# COMECA_TestSCH.net
KiCad netlist of a schematic drawn in Altium Designer
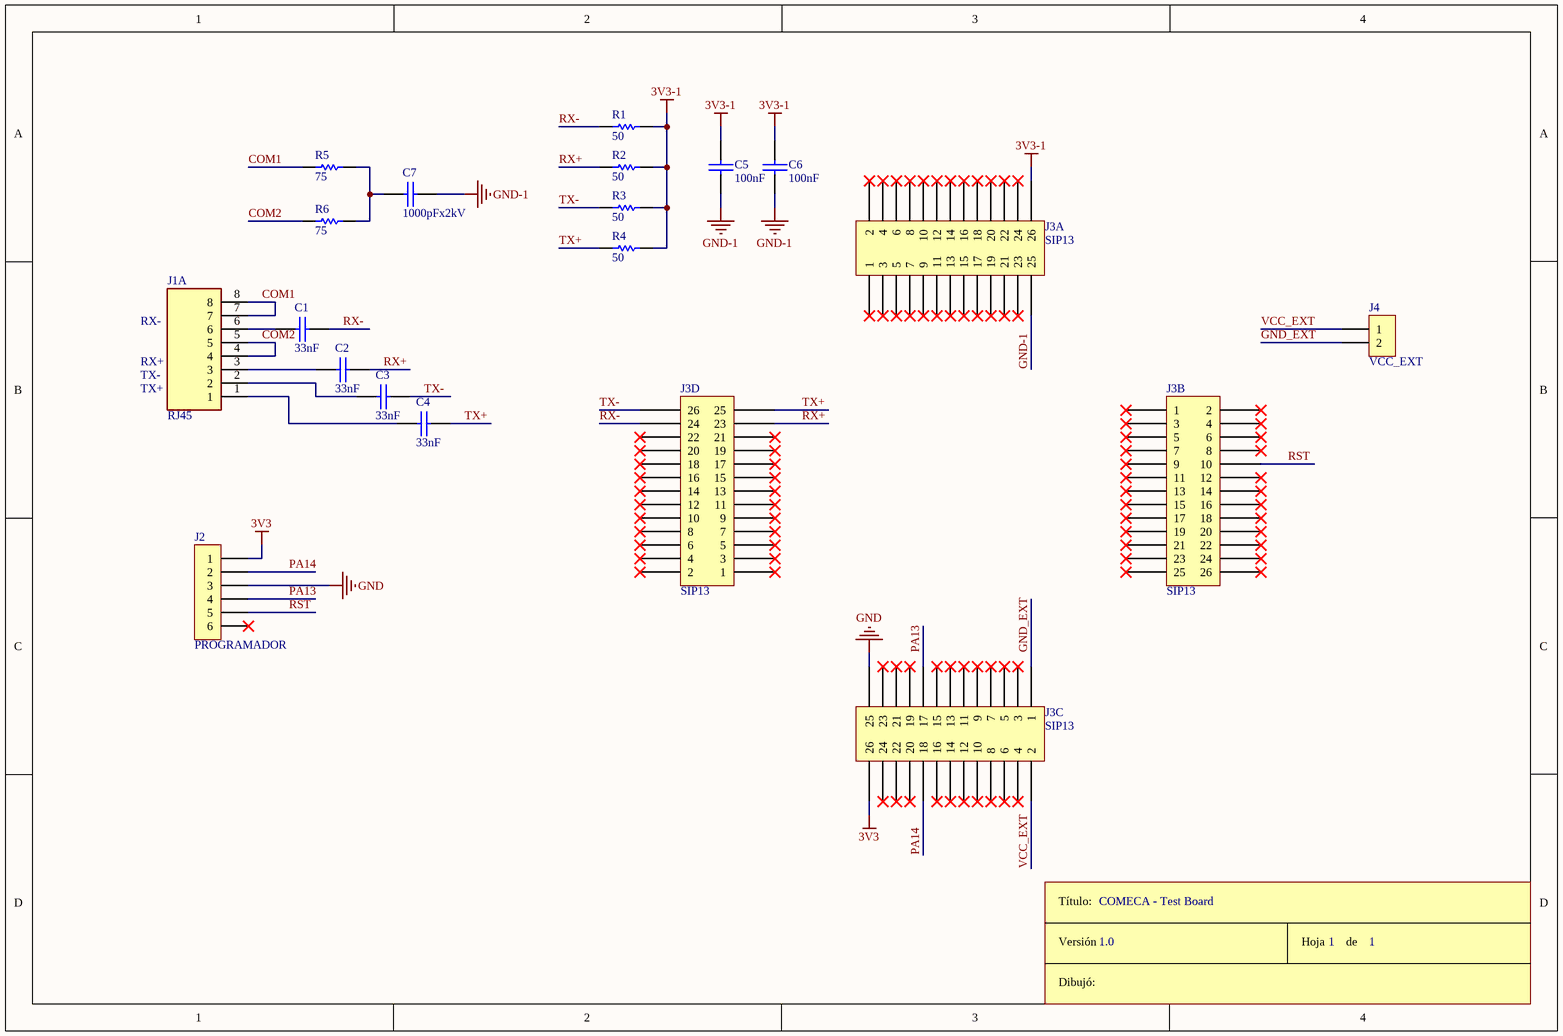
[diagram p0: COMECA_TestSCH.SchDoc]

(export (version "E")
  (design (tool "Eeschema 10.0.6"))
  (components
    (comp (ref "C1") (value "33nF") (footprint "CAP100") (libsource (lib "LIBEBAL") (part "CAP")))
    (comp (ref "C2") (value "33nF") (footprint "CAP100") (libsource (lib "LIBEBAL") (part "CAP")))
    (comp (ref "C3") (value "33nF") (footprint "CAP100") (libsource (lib "LIBEBAL") (part "CAP")))
    (comp (ref "C4") (value "33nF") (footprint "CAP100") (libsource (lib "LIBEBAL") (part "CAP")))
    (comp (ref "C5") (value "100nF") (footprint "CAP100") (libsource (lib "LIBEBAL") (part "CAP")))
    (comp (ref "C6") (value "100nF") (footprint "CAP100") (libsource (lib "LIBEBAL") (part "CAP")))
    (comp (ref "C7") (value "1000pFx2kV") (footprint "CAP100") (libsource (lib "LIBEBAL") (part "CAP")))
    (comp (ref "J1A")
      (value "RJ45")
      (footprint "CUI_CRJ032-1-TH")
      (description "8P8C, Single Port, Horizontal, Unshielded, No LED, Through Hole, RJ45 Modular Connector")
      (fields (field (name "MP") "CRJ032-1-TH") (field (name "MF") "CUI Devices"))
      (libsource (lib "CRJ032-1-TH") (part "CRJ032-1-TH"))
    )
    (comp (ref "J2") (value "PROGRAMADOR") (footprint "SIP6") (libsource (lib "LIBEBAL") (part "CON6")))
    (comp (ref "J3A")
      (value "SIP13")
      (footprint "SIP13*2 - HDR")
      (libsource (lib "AditionalComponents") (part "CON13*2"))
    )
    (comp (ref "J3B") (value "SIP13") (footprint "SIP13*2 - HDR") (libsource (lib "") (part "CON13*2_1")))
    (comp (ref "J3C") (value "SIP13") (footprint "SIP13*2 - HDR") (libsource (lib "") (part "CON13*2_3")))
    (comp (ref "J3D") (value "SIP13") (footprint "SIP13*2 - HDR") (libsource (lib "") (part "CON13*2_2")))
    (comp (ref "J4") (value "VCC_EXT") (footprint "SIP2") (libsource (lib "LIBEBAL") (part "CON2")))
    (comp (ref "R1") (value "50") (footprint "RES400") (libsource (lib "LIBEBAL") (part "RES")))
    (comp (ref "R2") (value "50") (footprint "RES400") (libsource (lib "LIBEBAL") (part "RES")))
    (comp (ref "R3") (value "50") (footprint "RES400") (libsource (lib "LIBEBAL") (part "RES")))
    (comp (ref "R4") (value "50") (footprint "RES400") (libsource (lib "LIBEBAL") (part "RES")))
    (comp (ref "R5") (value "75") (footprint "RES400") (libsource (lib "LIBEBAL") (part "RES")))
    (comp (ref "R6") (value "75") (footprint "RES400") (libsource (lib "LIBEBAL") (part "RES")))
    (comp (ref "ROT1") (value "Rótulo") (libsource (lib "LIB PIO IX") (part "Rótulo")))
  )
  (nets
    (net (code "1") (name "/COM1") (class "Default")
      (node (ref "J1A") (pin "7") (pinfunction "7_7") (pintype "passive"))
      (node (ref "J1A") (pin "8") (pinfunction "8_8") (pintype "passive"))
      (node (ref "R5") (pin "2") (pinfunction "2_2") (pintype "passive"))
    )
    (net (code "2") (name "/COM2") (class "Default")
      (node (ref "J1A") (pin "4") (pinfunction "4_4") (pintype "passive"))
      (node (ref "J1A") (pin "5") (pinfunction "5_5") (pintype "passive"))
      (node (ref "R6") (pin "1") (pinfunction "1_1") (pintype "passive"))
    )
    (net (code "3") (name "/GND_EXT") (class "Default")
      (node (ref "J3C") (pin "1") (pinfunction "1_1") (pintype "passive"))
      (node (ref "J4") (pin "2") (pinfunction "2_2") (pintype "passive"))
    )
    (net (code "4") (name "/PA13") (class "Default")
      (node (ref "J2") (pin "4") (pinfunction "4_4") (pintype "passive"))
      (node (ref "J3C") (pin "17") (pinfunction "17_17") (pintype "passive"))
    )
    (net (code "5") (name "/PA14") (class "Default")
      (node (ref "J2") (pin "2") (pinfunction "2_2") (pintype "passive"))
      (node (ref "J3C") (pin "18") (pinfunction "18_18") (pintype "passive"))
    )
    (net (code "6") (name "/RST") (class "Default")
      (node (ref "J2") (pin "5") (pinfunction "5_5") (pintype "passive"))
      (node (ref "J3B") (pin "10") (pinfunction "10_10") (pintype "passive"))
    )
    (net (code "7") (name "/RX+") (class "Default")
      (node (ref "C2") (pin "2") (pinfunction "2_2") (pintype "passive"))
      (node (ref "J3D") (pin "23") (pinfunction "23_23") (pintype "passive"))
      (node (ref "R2") (pin "1") (pinfunction "1_1") (pintype "passive"))
    )
    (net (code "8") (name "/RX-") (class "Default")
      (node (ref "C1") (pin "2") (pinfunction "2_2") (pintype "passive"))
      (node (ref "J3D") (pin "24") (pinfunction "24_24") (pintype "passive"))
      (node (ref "R1") (pin "1") (pinfunction "1_1") (pintype "passive"))
    )
    (net (code "9") (name "/TX+") (class "Default")
      (node (ref "C4") (pin "2") (pinfunction "2_2") (pintype "passive"))
      (node (ref "J3D") (pin "25") (pinfunction "25_25") (pintype "passive"))
      (node (ref "R4") (pin "1") (pinfunction "1_1") (pintype "passive"))
    )
    (net (code "10") (name "/TX-") (class "Default")
      (node (ref "C3") (pin "2") (pinfunction "2_2") (pintype "passive"))
      (node (ref "J3D") (pin "26") (pinfunction "26_26") (pintype "passive"))
      (node (ref "R3") (pin "1") (pinfunction "1_1") (pintype "passive"))
    )
    (net (code "11") (name "/VCC_EXT") (class "Default")
      (node (ref "J3C") (pin "2") (pinfunction "2_2") (pintype "passive"))
      (node (ref "J4") (pin "1") (pinfunction "1_1") (pintype "passive"))
    )
    (net (code "12") (name "3V3") (class "Default")
      (node (ref "J2") (pin "1") (pinfunction "1_1") (pintype "passive"))
      (node (ref "J3C") (pin "26") (pinfunction "26_26") (pintype "passive"))
    )
    (net (code "13") (name "3V3-1") (class "Default")
      (node (ref "C5") (pin "1") (pinfunction "1_1") (pintype "passive"))
      (node (ref "C6") (pin "1") (pinfunction "1_1") (pintype "passive"))
      (node (ref "J3A") (pin "26") (pinfunction "26_26") (pintype "passive"))
      (node (ref "R1") (pin "2") (pinfunction "2_2") (pintype "passive"))
      (node (ref "R2") (pin "2") (pinfunction "2_2") (pintype "passive"))
      (node (ref "R3") (pin "2") (pinfunction "2_2") (pintype "passive"))
      (node (ref "R4") (pin "2") (pinfunction "2_2") (pintype "passive"))
    )
    (net (code "14") (name "GND") (class "Default")
      (node (ref "J2") (pin "3") (pinfunction "3_3") (pintype "passive"))
      (node (ref "J3C") (pin "25") (pinfunction "25_25") (pintype "passive"))
    )
    (net (code "15") (name "GND-1") (class "Default")
      (node (ref "C5") (pin "2") (pinfunction "2_2") (pintype "passive"))
      (node (ref "C6") (pin "2") (pinfunction "2_2") (pintype "passive"))
      (node (ref "C7") (pin "2") (pinfunction "2_2") (pintype "passive"))
      (node (ref "J3A") (pin "25") (pinfunction "25_25") (pintype "passive"))
    )
    (net (code "16") (name "Net-(C1-Pad1)") (class "Default")
      (node (ref "C1") (pin "1") (pinfunction "1_1") (pintype "passive"))
      (node (ref "J1A") (pin "6") (pinfunction "6_6") (pintype "passive"))
    )
    (net (code "17") (name "Net-(C2-Pad1)") (class "Default")
      (node (ref "C2") (pin "1") (pinfunction "1_1") (pintype "passive"))
      (node (ref "J1A") (pin "3") (pinfunction "3_3") (pintype "passive"))
    )
    (net (code "18") (name "Net-(C3-Pad1)") (class "Default")
      (node (ref "C3") (pin "1") (pinfunction "1_1") (pintype "passive"))
      (node (ref "J1A") (pin "2") (pinfunction "2_2") (pintype "passive"))
    )
    (net (code "19") (name "Net-(C4-Pad1)") (class "Default")
      (node (ref "C4") (pin "1") (pinfunction "1_1") (pintype "passive"))
      (node (ref "J1A") (pin "1") (pinfunction "1_1") (pintype "passive"))
    )
    (net (code "20") (name "Net-(C7-Pad1)") (class "Default")
      (node (ref "C7") (pin "1") (pinfunction "1_1") (pintype "passive"))
      (node (ref "R5") (pin "1") (pinfunction "1_1") (pintype "passive"))
      (node (ref "R6") (pin "2") (pinfunction "2_2") (pintype "passive"))
    )
    (net (code "21") (name "unconnected-(J2-Pad6)") (class "Default")
      (node (ref "J2") (pin "6") (pinfunction "6_6") (pintype "passive+no_connect"))
    )
    (net (code "22") (name "unconnected-(J3A-Pad1)") (class "Default")
      (node (ref "J3A") (pin "1") (pinfunction "1_1") (pintype "passive+no_connect"))
    )
    (net (code "23") (name "unconnected-(J3A-Pad2)") (class "Default")
      (node (ref "J3A") (pin "2") (pinfunction "2_2") (pintype "passive+no_connect"))
    )
    (net (code "24") (name "unconnected-(J3A-Pad3)") (class "Default")
      (node (ref "J3A") (pin "3") (pinfunction "3_3") (pintype "passive+no_connect"))
    )
    (net (code "25") (name "unconnected-(J3A-Pad4)") (class "Default")
      (node (ref "J3A") (pin "4") (pinfunction "4_4") (pintype "passive+no_connect"))
    )
    (net (code "26") (name "unconnected-(J3A-Pad5)") (class "Default")
      (node (ref "J3A") (pin "5") (pinfunction "5_5") (pintype "passive+no_connect"))
    )
    (net (code "27") (name "unconnected-(J3A-Pad6)") (class "Default")
      (node (ref "J3A") (pin "6") (pinfunction "6_6") (pintype "passive+no_connect"))
    )
    (net (code "28") (name "unconnected-(J3A-Pad7)") (class "Default")
      (node (ref "J3A") (pin "7") (pinfunction "7_7") (pintype "passive+no_connect"))
    )
    (net (code "29") (name "unconnected-(J3A-Pad8)") (class "Default")
      (node (ref "J3A") (pin "8") (pinfunction "8_8") (pintype "passive+no_connect"))
    )
    (net (code "30") (name "unconnected-(J3A-Pad9)") (class "Default")
      (node (ref "J3A") (pin "9") (pinfunction "9_9") (pintype "passive+no_connect"))
    )
    (net (code "31") (name "unconnected-(J3A-Pad10)") (class "Default")
      (node (ref "J3A") (pin "10") (pinfunction "10_10") (pintype "passive+no_connect"))
    )
    (net (code "32") (name "unconnected-(J3A-Pad11)") (class "Default")
      (node (ref "J3A") (pin "11") (pinfunction "11_11") (pintype "passive+no_connect"))
    )
    (net (code "33") (name "unconnected-(J3A-Pad12)") (class "Default")
      (node (ref "J3A") (pin "12") (pinfunction "12_12") (pintype "passive+no_connect"))
    )
    (net (code "34") (name "unconnected-(J3A-Pad13)") (class "Default")
      (node (ref "J3A") (pin "13") (pinfunction "13_13") (pintype "passive+no_connect"))
    )
    (net (code "35") (name "unconnected-(J3A-Pad14)") (class "Default")
      (node (ref "J3A") (pin "14") (pinfunction "14_14") (pintype "passive+no_connect"))
    )
    (net (code "36") (name "unconnected-(J3A-Pad15)") (class "Default")
      (node (ref "J3A") (pin "15") (pinfunction "15_15") (pintype "passive+no_connect"))
    )
    (net (code "37") (name "unconnected-(J3A-Pad16)") (class "Default")
      (node (ref "J3A") (pin "16") (pinfunction "16_16") (pintype "passive+no_connect"))
    )
    (net (code "38") (name "unconnected-(J3A-Pad17)") (class "Default")
      (node (ref "J3A") (pin "17") (pinfunction "17_17") (pintype "passive+no_connect"))
    )
    (net (code "39") (name "unconnected-(J3A-Pad18)") (class "Default")
      (node (ref "J3A") (pin "18") (pinfunction "18_18") (pintype "passive+no_connect"))
    )
    (net (code "40") (name "unconnected-(J3A-Pad19)") (class "Default")
      (node (ref "J3A") (pin "19") (pinfunction "19_19") (pintype "passive+no_connect"))
    )
    (net (code "41") (name "unconnected-(J3A-Pad20)") (class "Default")
      (node (ref "J3A") (pin "20") (pinfunction "20_20") (pintype "passive+no_connect"))
    )
    (net (code "42") (name "unconnected-(J3A-Pad21)") (class "Default")
      (node (ref "J3A") (pin "21") (pinfunction "21_21") (pintype "passive+no_connect"))
    )
    (net (code "43") (name "unconnected-(J3A-Pad22)") (class "Default")
      (node (ref "J3A") (pin "22") (pinfunction "22_22") (pintype "passive+no_connect"))
    )
    (net (code "44") (name "unconnected-(J3A-Pad23)") (class "Default")
      (node (ref "J3A") (pin "23") (pinfunction "23_23") (pintype "passive+no_connect"))
    )
    (net (code "45") (name "unconnected-(J3A-Pad24)") (class "Default")
      (node (ref "J3A") (pin "24") (pinfunction "24_24") (pintype "passive+no_connect"))
    )
    (net (code "46") (name "unconnected-(J3B-Pad1)") (class "Default")
      (node (ref "J3B") (pin "1") (pinfunction "1_1") (pintype "passive+no_connect"))
    )
    (net (code "47") (name "unconnected-(J3B-Pad2)") (class "Default")
      (node (ref "J3B") (pin "2") (pinfunction "2_2") (pintype "passive+no_connect"))
    )
    (net (code "48") (name "unconnected-(J3B-Pad3)") (class "Default")
      (node (ref "J3B") (pin "3") (pinfunction "3_3") (pintype "passive+no_connect"))
    )
    (net (code "49") (name "unconnected-(J3B-Pad4)") (class "Default")
      (node (ref "J3B") (pin "4") (pinfunction "4_4") (pintype "passive+no_connect"))
    )
    (net (code "50") (name "unconnected-(J3B-Pad5)") (class "Default")
      (node (ref "J3B") (pin "5") (pinfunction "5_5") (pintype "passive+no_connect"))
    )
    (net (code "51") (name "unconnected-(J3B-Pad6)") (class "Default")
      (node (ref "J3B") (pin "6") (pinfunction "6_6") (pintype "passive+no_connect"))
    )
    (net (code "52") (name "unconnected-(J3B-Pad7)") (class "Default")
      (node (ref "J3B") (pin "7") (pinfunction "7_7") (pintype "passive+no_connect"))
    )
    (net (code "53") (name "unconnected-(J3B-Pad8)") (class "Default")
      (node (ref "J3B") (pin "8") (pinfunction "8_8") (pintype "passive+no_connect"))
    )
    (net (code "54") (name "unconnected-(J3B-Pad9)") (class "Default")
      (node (ref "J3B") (pin "9") (pinfunction "9_9") (pintype "passive+no_connect"))
    )
    (net (code "55") (name "unconnected-(J3B-Pad11)") (class "Default")
      (node (ref "J3B") (pin "11") (pinfunction "11_11") (pintype "passive+no_connect"))
    )
    (net (code "56") (name "unconnected-(J3B-Pad12)") (class "Default")
      (node (ref "J3B") (pin "12") (pinfunction "12_12") (pintype "passive+no_connect"))
    )
    (net (code "57") (name "unconnected-(J3B-Pad13)") (class "Default")
      (node (ref "J3B") (pin "13") (pinfunction "13_13") (pintype "passive+no_connect"))
    )
    (net (code "58") (name "unconnected-(J3B-Pad14)") (class "Default")
      (node (ref "J3B") (pin "14") (pinfunction "14_14") (pintype "passive+no_connect"))
    )
    (net (code "59") (name "unconnected-(J3B-Pad15)") (class "Default")
      (node (ref "J3B") (pin "15") (pinfunction "15_15") (pintype "passive+no_connect"))
    )
    (net (code "60") (name "unconnected-(J3B-Pad16)") (class "Default")
      (node (ref "J3B") (pin "16") (pinfunction "16_16") (pintype "passive+no_connect"))
    )
    (net (code "61") (name "unconnected-(J3B-Pad17)") (class "Default")
      (node (ref "J3B") (pin "17") (pinfunction "17_17") (pintype "passive+no_connect"))
    )
    (net (code "62") (name "unconnected-(J3B-Pad18)") (class "Default")
      (node (ref "J3B") (pin "18") (pinfunction "18_18") (pintype "passive+no_connect"))
    )
    (net (code "63") (name "unconnected-(J3B-Pad19)") (class "Default")
      (node (ref "J3B") (pin "19") (pinfunction "19_19") (pintype "passive+no_connect"))
    )
    (net (code "64") (name "unconnected-(J3B-Pad20)") (class "Default")
      (node (ref "J3B") (pin "20") (pinfunction "20_20") (pintype "passive+no_connect"))
    )
    (net (code "65") (name "unconnected-(J3B-Pad21)") (class "Default")
      (node (ref "J3B") (pin "21") (pinfunction "21_21") (pintype "passive+no_connect"))
    )
    (net (code "66") (name "unconnected-(J3B-Pad22)") (class "Default")
      (node (ref "J3B") (pin "22") (pinfunction "22_22") (pintype "passive+no_connect"))
    )
    (net (code "67") (name "unconnected-(J3B-Pad23)") (class "Default")
      (node (ref "J3B") (pin "23") (pinfunction "23_23") (pintype "passive+no_connect"))
    )
    (net (code "68") (name "unconnected-(J3B-Pad24)") (class "Default")
      (node (ref "J3B") (pin "24") (pinfunction "24_24") (pintype "passive+no_connect"))
    )
    (net (code "69") (name "unconnected-(J3B-Pad25)") (class "Default")
      (node (ref "J3B") (pin "25") (pinfunction "25_25") (pintype "passive+no_connect"))
    )
    (net (code "70") (name "unconnected-(J3B-Pad26)") (class "Default")
      (node (ref "J3B") (pin "26") (pinfunction "26_26") (pintype "passive+no_connect"))
    )
    (net (code "71") (name "unconnected-(J3C-Pad3)") (class "Default")
      (node (ref "J3C") (pin "3") (pinfunction "3_3") (pintype "passive+no_connect"))
    )
    (net (code "72") (name "unconnected-(J3C-Pad4)") (class "Default")
      (node (ref "J3C") (pin "4") (pinfunction "4_4") (pintype "passive+no_connect"))
    )
    (net (code "73") (name "unconnected-(J3C-Pad5)") (class "Default")
      (node (ref "J3C") (pin "5") (pinfunction "5_5") (pintype "passive+no_connect"))
    )
    (net (code "74") (name "unconnected-(J3C-Pad6)") (class "Default")
      (node (ref "J3C") (pin "6") (pinfunction "6_6") (pintype "passive+no_connect"))
    )
    (net (code "75") (name "unconnected-(J3C-Pad7)") (class "Default")
      (node (ref "J3C") (pin "7") (pinfunction "7_7") (pintype "passive+no_connect"))
    )
    (net (code "76") (name "unconnected-(J3C-Pad8)") (class "Default")
      (node (ref "J3C") (pin "8") (pinfunction "8_8") (pintype "passive+no_connect"))
    )
    (net (code "77") (name "unconnected-(J3C-Pad9)") (class "Default")
      (node (ref "J3C") (pin "9") (pinfunction "9_9") (pintype "passive+no_connect"))
    )
    (net (code "78") (name "unconnected-(J3C-Pad10)") (class "Default")
      (node (ref "J3C") (pin "10") (pinfunction "10_10") (pintype "passive+no_connect"))
    )
    (net (code "79") (name "unconnected-(J3C-Pad11)") (class "Default")
      (node (ref "J3C") (pin "11") (pinfunction "11_11") (pintype "passive+no_connect"))
    )
    (net (code "80") (name "unconnected-(J3C-Pad12)") (class "Default")
      (node (ref "J3C") (pin "12") (pinfunction "12_12") (pintype "passive+no_connect"))
    )
    (net (code "81") (name "unconnected-(J3C-Pad13)") (class "Default")
      (node (ref "J3C") (pin "13") (pinfunction "13_13") (pintype "passive+no_connect"))
    )
    (net (code "82") (name "unconnected-(J3C-Pad14)") (class "Default")
      (node (ref "J3C") (pin "14") (pinfunction "14_14") (pintype "passive+no_connect"))
    )
    (net (code "83") (name "unconnected-(J3C-Pad15)") (class "Default")
      (node (ref "J3C") (pin "15") (pinfunction "15_15") (pintype "passive+no_connect"))
    )
    (net (code "84") (name "unconnected-(J3C-Pad16)") (class "Default")
      (node (ref "J3C") (pin "16") (pinfunction "16_16") (pintype "passive+no_connect"))
    )
    (net (code "85") (name "unconnected-(J3C-Pad19)") (class "Default")
      (node (ref "J3C") (pin "19") (pinfunction "19_19") (pintype "passive+no_connect"))
    )
    (net (code "86") (name "unconnected-(J3C-Pad20)") (class "Default")
      (node (ref "J3C") (pin "20") (pinfunction "20_20") (pintype "passive+no_connect"))
    )
    (net (code "87") (name "unconnected-(J3C-Pad21)") (class "Default")
      (node (ref "J3C") (pin "21") (pinfunction "21_21") (pintype "passive+no_connect"))
    )
    (net (code "88") (name "unconnected-(J3C-Pad22)") (class "Default")
      (node (ref "J3C") (pin "22") (pinfunction "22_22") (pintype "passive+no_connect"))
    )
    (net (code "89") (name "unconnected-(J3C-Pad23)") (class "Default")
      (node (ref "J3C") (pin "23") (pinfunction "23_23") (pintype "passive+no_connect"))
    )
    (net (code "90") (name "unconnected-(J3C-Pad24)") (class "Default")
      (node (ref "J3C") (pin "24") (pinfunction "24_24") (pintype "passive+no_connect"))
    )
    (net (code "91") (name "unconnected-(J3D-Pad1)") (class "Default")
      (node (ref "J3D") (pin "1") (pinfunction "1_1") (pintype "passive+no_connect"))
    )
    (net (code "92") (name "unconnected-(J3D-Pad2)") (class "Default")
      (node (ref "J3D") (pin "2") (pinfunction "2_2") (pintype "passive+no_connect"))
    )
    (net (code "93") (name "unconnected-(J3D-Pad3)") (class "Default")
      (node (ref "J3D") (pin "3") (pinfunction "3_3") (pintype "passive+no_connect"))
    )
    (net (code "94") (name "unconnected-(J3D-Pad4)") (class "Default")
      (node (ref "J3D") (pin "4") (pinfunction "4_4") (pintype "passive+no_connect"))
    )
    (net (code "95") (name "unconnected-(J3D-Pad5)") (class "Default")
      (node (ref "J3D") (pin "5") (pinfunction "5_5") (pintype "passive+no_connect"))
    )
    (net (code "96") (name "unconnected-(J3D-Pad6)") (class "Default")
      (node (ref "J3D") (pin "6") (pinfunction "6_6") (pintype "passive+no_connect"))
    )
    (net (code "97") (name "unconnected-(J3D-Pad7)") (class "Default")
      (node (ref "J3D") (pin "7") (pinfunction "7_7") (pintype "passive+no_connect"))
    )
    (net (code "98") (name "unconnected-(J3D-Pad8)") (class "Default")
      (node (ref "J3D") (pin "8") (pinfunction "8_8") (pintype "passive+no_connect"))
    )
    (net (code "99") (name "unconnected-(J3D-Pad9)") (class "Default")
      (node (ref "J3D") (pin "9") (pinfunction "9_9") (pintype "passive+no_connect"))
    )
    (net (code "100") (name "unconnected-(J3D-Pad10)") (class "Default")
      (node (ref "J3D") (pin "10") (pinfunction "10_10") (pintype "passive+no_connect"))
    )
    (net (code "101") (name "unconnected-(J3D-Pad11)") (class "Default")
      (node (ref "J3D") (pin "11") (pinfunction "11_11") (pintype "passive+no_connect"))
    )
    (net (code "102") (name "unconnected-(J3D-Pad12)") (class "Default")
      (node (ref "J3D") (pin "12") (pinfunction "12_12") (pintype "passive+no_connect"))
    )
    (net (code "103") (name "unconnected-(J3D-Pad13)") (class "Default")
      (node (ref "J3D") (pin "13") (pinfunction "13_13") (pintype "passive+no_connect"))
    )
    (net (code "104") (name "unconnected-(J3D-Pad14)") (class "Default")
      (node (ref "J3D") (pin "14") (pinfunction "14_14") (pintype "passive+no_connect"))
    )
    (net (code "105") (name "unconnected-(J3D-Pad15)") (class "Default")
      (node (ref "J3D") (pin "15") (pinfunction "15_15") (pintype "passive+no_connect"))
    )
    (net (code "106") (name "unconnected-(J3D-Pad16)") (class "Default")
      (node (ref "J3D") (pin "16") (pinfunction "16_16") (pintype "passive+no_connect"))
    )
    (net (code "107") (name "unconnected-(J3D-Pad17)") (class "Default")
      (node (ref "J3D") (pin "17") (pinfunction "17_17") (pintype "passive+no_connect"))
    )
    (net (code "108") (name "unconnected-(J3D-Pad18)") (class "Default")
      (node (ref "J3D") (pin "18") (pinfunction "18_18") (pintype "passive+no_connect"))
    )
    (net (code "109") (name "unconnected-(J3D-Pad19)") (class "Default")
      (node (ref "J3D") (pin "19") (pinfunction "19_19") (pintype "passive+no_connect"))
    )
    (net (code "110") (name "unconnected-(J3D-Pad20)") (class "Default")
      (node (ref "J3D") (pin "20") (pinfunction "20_20") (pintype "passive+no_connect"))
    )
    (net (code "111") (name "unconnected-(J3D-Pad21)") (class "Default")
      (node (ref "J3D") (pin "21") (pinfunction "21_21") (pintype "passive+no_connect"))
    )
    (net (code "112") (name "unconnected-(J3D-Pad22)") (class "Default")
      (node (ref "J3D") (pin "22") (pinfunction "22_22") (pintype "passive+no_connect"))
    )
  )
)
